# smart_switch_2021-06-13.net
KiCad netlist of a schematic drawn in EasyEDA
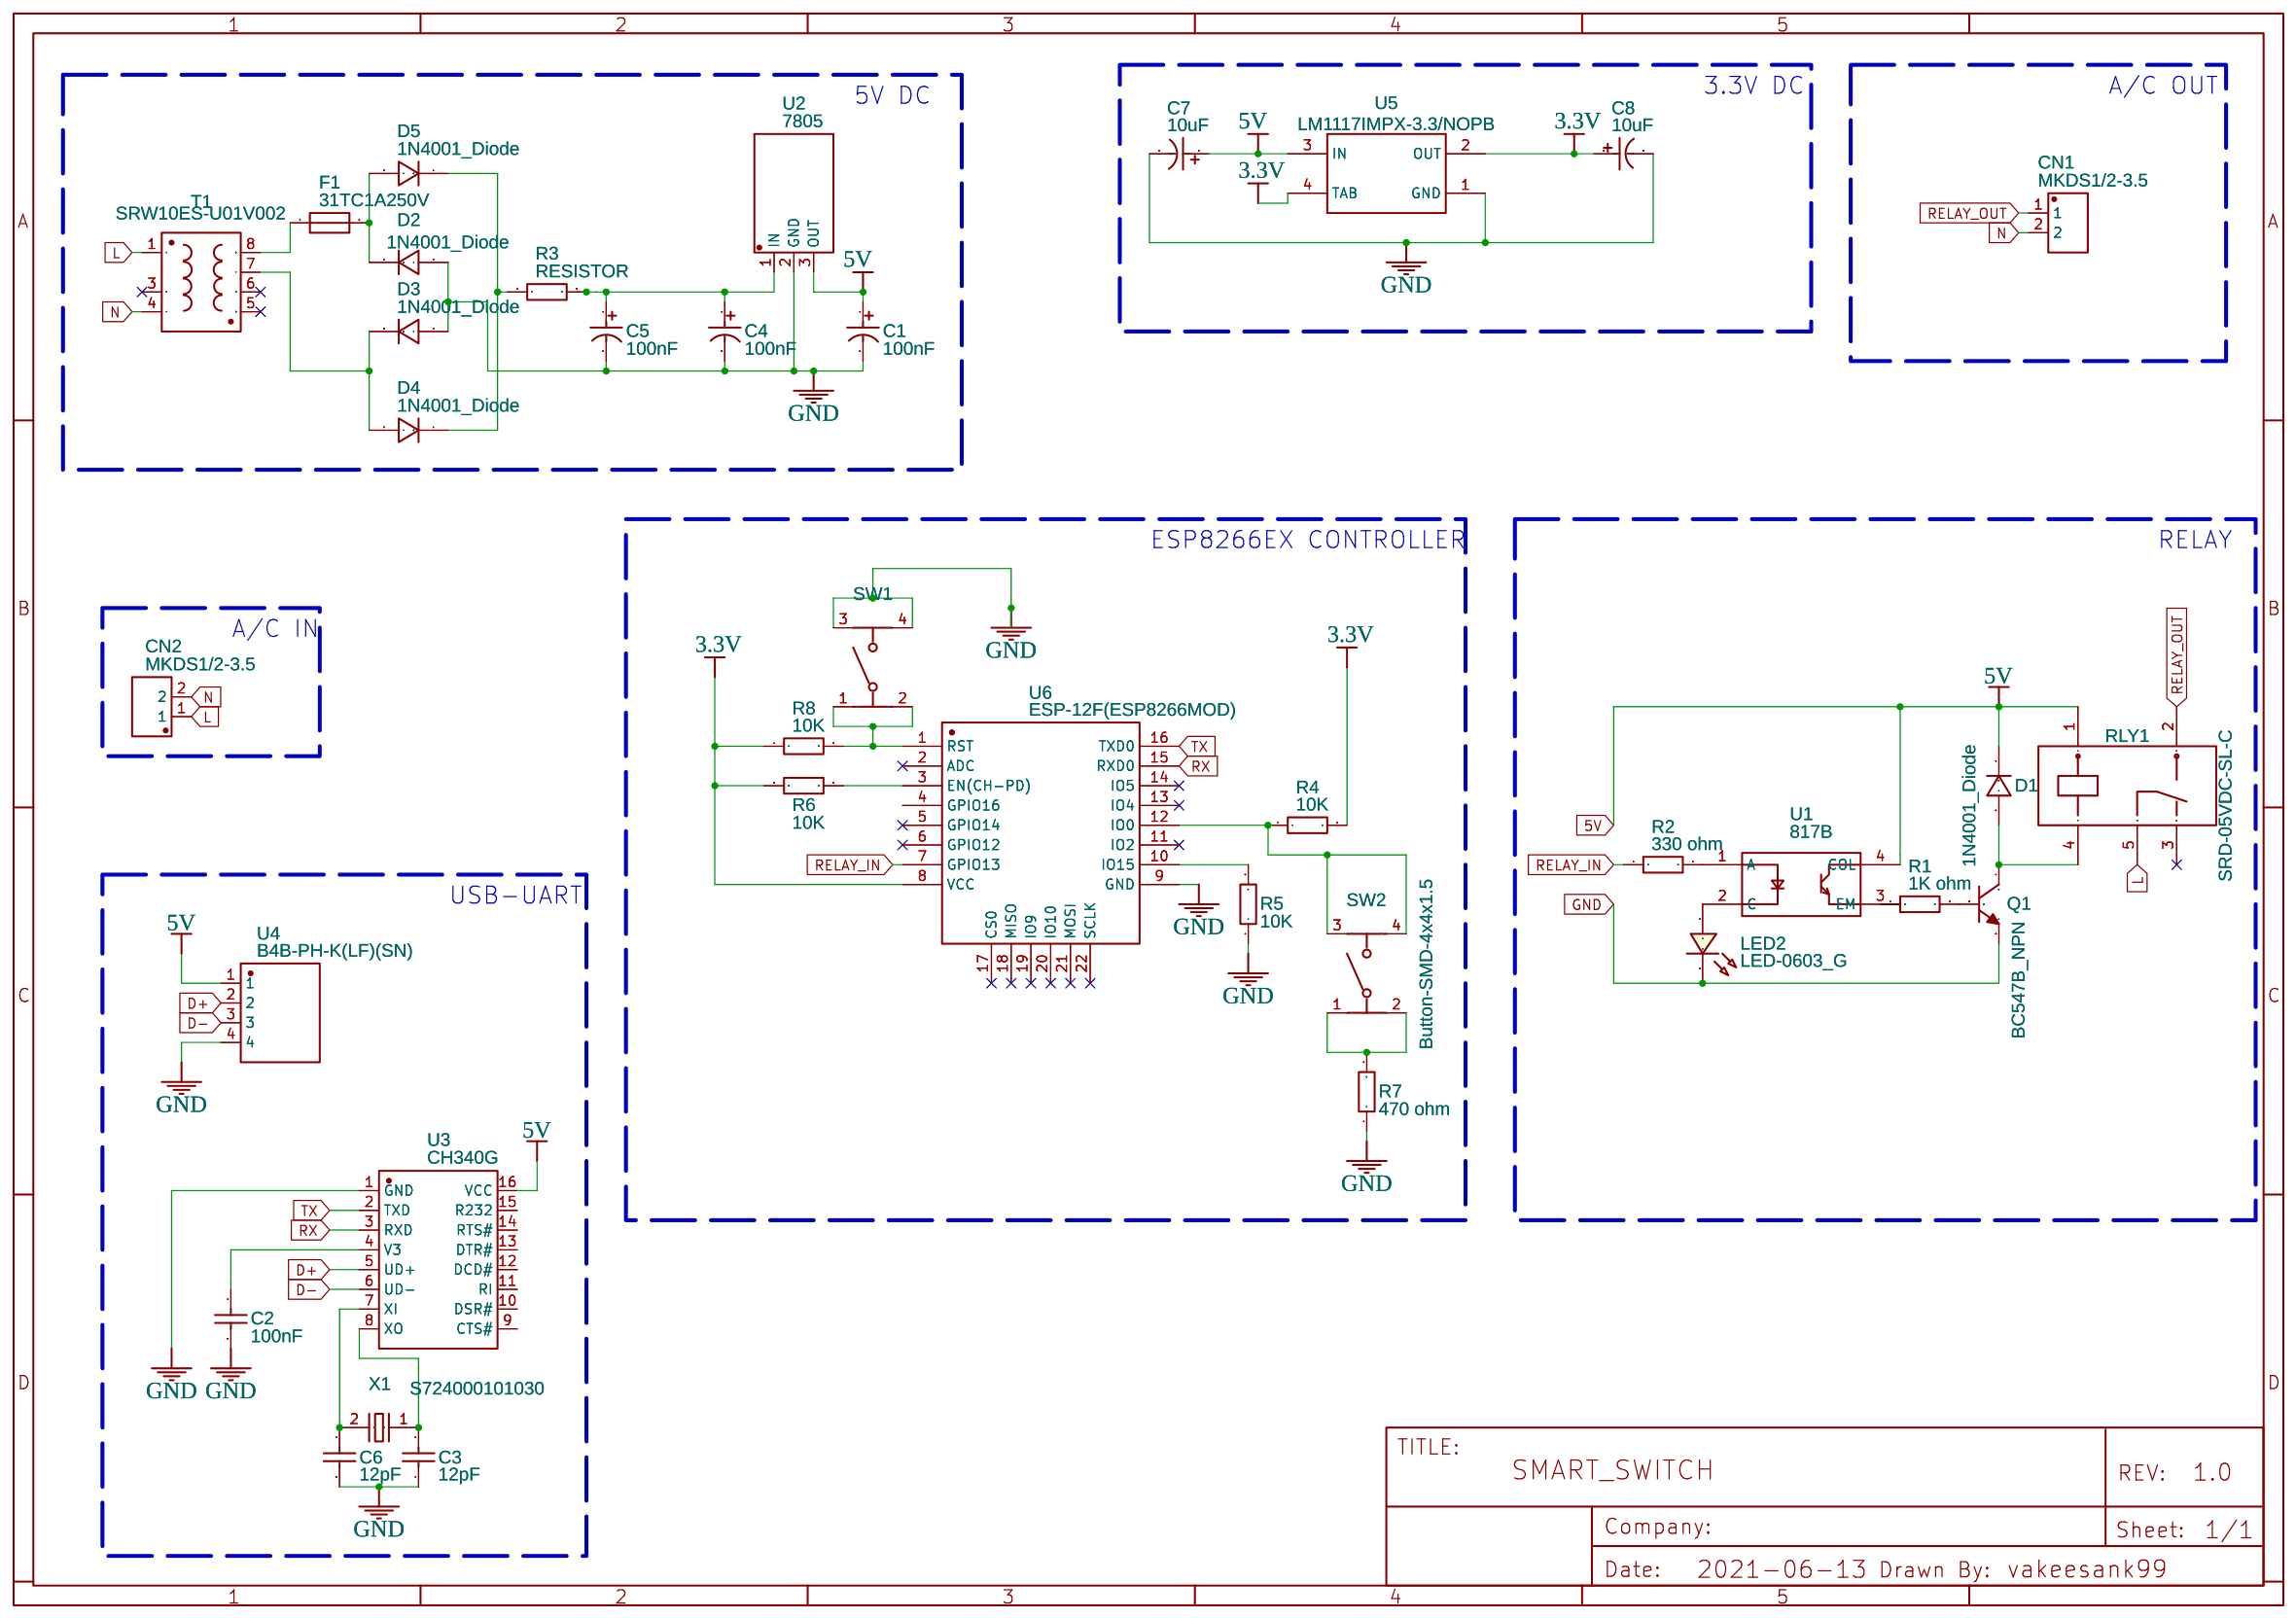
[diagram p0: schematic sheet]

(export (version "E")
  (design (tool "Eeschema 10.0.6"))
  (components
    (comp (ref "C1")
      (value "100nF")
      (fields (field (name "BOM_Manufacturer Part") "0.1UF 50V") (field (name "BOM_Supplier Part") "C28061"))
      (libsource (lib "") (part "0.1uF"))
    )
    (comp (ref "C2")
      (value "100nF")
      (fields
        (field (name "BOM_Manufacturer Part") "0.1UF(104) +-20% 63v")
        (field (name "BOM_Supplier Part") "C19355")
      )
      (libsource (lib "") (part "100nF"))
    )
    (comp (ref "C3")
      (value "12pF")
      (fields
        (field (name "BOM_Manufacturer Part") "0805CG120J500NT")
        (field (name "BOM_Supplier Part") "C38142")
      )
      (libsource (lib "") (part "0805CG120J500NT_C38142"))
    )
    (comp (ref "C4")
      (value "100nF")
      (fields (field (name "BOM_Manufacturer Part") "0.1UF 50V") (field (name "BOM_Supplier Part") "C28061"))
      (libsource (lib "") (part "0.1uF"))
    )
    (comp (ref "C5")
      (value "100nF")
      (fields (field (name "BOM_Manufacturer Part") "0.1UF 50V") (field (name "BOM_Supplier Part") "C28061"))
      (libsource (lib "") (part "0.1uF"))
    )
    (comp (ref "C6")
      (value "12pF")
      (fields
        (field (name "BOM_Manufacturer Part") "0805CG120J500NT")
        (field (name "BOM_Supplier Part") "C38142")
      )
      (libsource (lib "") (part "0805CG120J500NT_C38142"))
    )
    (comp (ref "C7")
      (value "10uF")
      (fields
        (field (name "BOM_Manufacturer Part") "10uF 16V 5*11")
        (field (name "BOM_Supplier Part") "C43799")
      )
      (libsource (lib "") (part "10uF 16V 5*11_1"))
    )
    (comp (ref "C8")
      (value "10uF")
      (fields
        (field (name "BOM_Manufacturer Part") "10uF 16V 5*11")
        (field (name "BOM_Supplier Part") "C43799")
      )
      (libsource (lib "") (part "10uF 16V 5*11"))
    )
    (comp (ref "CN1")
      (value "MKDS1/2-3.5")
      (fields (field (name "BOM_Supplier Part") "C89122"))
      (libsource (lib "") (part "MKDS1/2-3.5"))
    )
    (comp (ref "CN2")
      (value "MKDS1/2-3.5")
      (fields (field (name "BOM_Supplier Part") "C89122"))
      (libsource (lib "") (part "MKDS1/2-3.5_1"))
    )
    (comp (ref "D1")
      (value "1N4001_Diode")
      (fields (field (name "BOM_Manufacturer Part") "1N4001-T") (field (name "BOM_Supplier Part") "C99656"))
      (libsource (lib "") (part "1N4001_Diode_2"))
    )
    (comp (ref "D2")
      (value "1N4001_Diode")
      (fields (field (name "BOM_Manufacturer Part") "1N4001-T") (field (name "BOM_Supplier Part") "C99656"))
      (libsource (lib "") (part "1N4001_Diode"))
    )
    (comp (ref "D3")
      (value "1N4001_Diode")
      (fields (field (name "BOM_Manufacturer Part") "1N4001-T") (field (name "BOM_Supplier Part") "C99656"))
      (libsource (lib "") (part "1N4001_Diode"))
    )
    (comp (ref "D4")
      (value "1N4001_Diode")
      (fields (field (name "BOM_Manufacturer Part") "1N4001-T") (field (name "BOM_Supplier Part") "C99656"))
      (libsource (lib "") (part "1N4001_Diode_1"))
    )
    (comp (ref "D5")
      (value "1N4001_Diode")
      (fields (field (name "BOM_Manufacturer Part") "1N4001-T") (field (name "BOM_Supplier Part") "C99656"))
      (libsource (lib "") (part "1N4001_Diode_1"))
    )
    (comp (ref "F1")
      (value "31TC1A250V")
      (fields (field (name "BOM_Supplier Part") "C529652"))
      (libsource (lib "") (part "31TC1A250V"))
    )
    (comp (ref "LED2")
      (value "LED-0603_G")
      (fields
        (field (name "BOM_Manufacturer Part") "19-217/GHC-YR1S2/3T")
        (field (name "BOM_Supplier Part") "C72043")
      )
      (libsource (lib "") (part "LED-0603_G"))
    )
    (comp (ref "Q1")
      (value "BC547B_NPN")
      (fields (field (name "BOM_Manufacturer Part") "BC547B") (field (name "BOM_Supplier Part") "C713613"))
      (libsource (lib "") (part "BC547B_NPN_Transistor"))
    )
    (comp (ref "R1")
      (value "1K ohm")
      (fields
        (field (name "BOM_Manufacturer Part") "MFR0W4F2200A50")
        (field (name "BOM_Supplier Part") "E57439")
      )
      (libsource (lib "") (part "RESISTOR"))
    )
    (comp (ref "R2")
      (value "330 ohm")
      (fields
        (field (name "BOM_Manufacturer Part") "MFR0W4F2200A50")
        (field (name "BOM_Supplier Part") "E57439")
      )
      (libsource (lib "") (part "RESISTOR"))
    )
    (comp (ref "R3")
      (value "RESISTOR")
      (fields
        (field (name "BOM_Manufacturer Part") "MFR0W4F2200A50")
        (field (name "BOM_Supplier Part") "E57439")
      )
      (libsource (lib "") (part "RESISTOR"))
    )
    (comp (ref "R4")
      (value "10K")
      (fields
        (field (name "BOM_Manufacturer Part") "TR0402D10KQ1025")
        (field (name "BOM_Supplier Part") "C149898")
      )
      (libsource (lib "") (part "TR0402D10KQ1025_1"))
    )
    (comp (ref "R5")
      (value "10K")
      (fields
        (field (name "BOM_Manufacturer Part") "TR0402D10KQ1025")
        (field (name "BOM_Supplier Part") "C149898")
      )
      (libsource (lib "") (part "TR0402D10KQ1025"))
    )
    (comp (ref "R6")
      (value "10K")
      (fields
        (field (name "BOM_Manufacturer Part") "TR0402D10KQ1025")
        (field (name "BOM_Supplier Part") "C149898")
      )
      (libsource (lib "") (part "TR0402D10KQ1025_2"))
    )
    (comp (ref "R7")
      (value "470 ohm")
      (fields
        (field (name "BOM_Manufacturer Part") "TR0402D10KQ1025")
        (field (name "BOM_Supplier Part") "C149898")
      )
      (libsource (lib "") (part "TR0402D10KQ1025"))
    )
    (comp (ref "R8")
      (value "10K")
      (fields
        (field (name "BOM_Manufacturer Part") "TR0402D10KQ1025")
        (field (name "BOM_Supplier Part") "C149898")
      )
      (libsource (lib "") (part "TR0402D10KQ1025_1"))
    )
    (comp (ref "RLY1")
      (value "SRD-05VDC-SL-C")
      (fields (field (name "BOM_Supplier Part") "C35449"))
      (libsource (lib "") (part "SRD-05VDC-SL-C"))
    )
    (comp (ref "SW1")
      (value "Button-SMD-4x4x1.5")
      (fields
        (field (name "BOM_Manufacturer Part") "4*4*1.5Copper head,260G, 0.25mm,")
        (field (name "BOM_Supplier Part") "C71830")
      )
      (libsource (lib "") (part "Button-SMD-4x4x1.5"))
    )
    (comp (ref "SW2")
      (value "Button-SMD-4x4x1.5")
      (fields
        (field (name "BOM_Manufacturer Part") "4*4*1.5Copper head,260G, 0.25mm,")
        (field (name "BOM_Supplier Part") "C71830")
      )
      (libsource (lib "") (part "Button-SMD-4x4x1.5"))
    )
    (comp (ref "T1")
      (value "SRW10ES-U01V002")
      (fields (field (name "BOM_Supplier Part") "C433047"))
      (libsource (lib "") (part "SRW10ES-U01V002"))
    )
    (comp (ref "U1")
      (value "817B")
      (fields (field (name "BOM_Supplier Part") "C695830"))
      (libsource (lib "") (part "817B"))
    )
    (comp (ref "U2")
      (value "7805")
      (fields (field (name "BOM_Supplier Part") "C305416"))
      (libsource (lib "") (part "7805"))
    )
    (comp (ref "U3")
      (value "CH340G")
      (fields (field (name "BOM_Supplier Part") "C14267"))
      (libsource (lib "") (part "CH340G"))
    )
    (comp (ref "U4")
      (value "B4B-PH-K(LF)(SN)")
      (fields (field (name "BOM_Supplier Part") "C265289"))
      (libsource (lib "") (part "B4B-PH-K(LF)(SN)"))
    )
    (comp (ref "U5")
      (value "LM1117IMPX-3.3/NOPB")
      (fields (field (name "BOM_Supplier Part") "C23984"))
      (libsource (lib "") (part "LM1117IMPX-3.3/NOPB"))
    )
    (comp (ref "U6")
      (value "ESP-12F(ESP8266MOD)")
      (fields (field (name "BOM_Supplier Part") "C82891"))
      (libsource (lib "") (part "ESP-12F(ESP8266MOD)"))
    )
    (comp (ref "X1")
      (value "S724000101030")
      (fields (field (name "BOM_Supplier Part") "C555584"))
      (libsource (lib "") (part "S724000101030"))
    )
  )
  (nets
    (net (code "1") (name "3.3V") (class "Default")
      (node (ref "C8") (pin "1") (pinfunction "1_1") (pintype "input"))
      (node (ref "R4") (pin "2") (pinfunction "2_2") (pintype "unspecified"))
      (node (ref "R6") (pin "2") (pinfunction "2_2") (pintype "unspecified"))
      (node (ref "R8") (pin "1") (pinfunction "1_1") (pintype "unspecified"))
      (node (ref "U5") (pin "2") (pinfunction "OUT_2") (pintype "passive"))
      (node (ref "U5") (pin "4") (pinfunction "TAB_4") (pintype "passive"))
      (node (ref "U6") (pin "8") (pinfunction "VCC_8") (pintype "unspecified"))
    )
    (net (code "2") (name "5V") (class "Default")
      (node (ref "C1") (pin "1") (pinfunction "1_1") (pintype "input"))
      (node (ref "C7") (pin "1") (pinfunction "1_1") (pintype "input"))
      (node (ref "D1") (pin "1") (pinfunction "C_1") (pintype "unspecified"))
      (node (ref "RLY1") (pin "1") (pinfunction "1_1") (pintype "input"))
      (node (ref "U1") (pin "4") (pinfunction "COL_4") (pintype "unspecified"))
      (node (ref "U2") (pin "3") (pinfunction "OUT_3") (pintype "unspecified"))
      (node (ref "U3") (pin "16") (pinfunction "VCC_16") (pintype "unspecified"))
      (node (ref "U4") (pin "1") (pinfunction "1_1") (pintype "unspecified"))
      (node (ref "U5") (pin "3") (pinfunction "IN_3") (pintype "passive"))
    )
    (net (code "3") (name "D+") (class "Default")
      (node (ref "U3") (pin "5") (pinfunction "UD+_5") (pintype "unspecified"))
      (node (ref "U4") (pin "2") (pinfunction "2_2") (pintype "unspecified"))
    )
    (net (code "4") (name "D-") (class "Default")
      (node (ref "U3") (pin "6") (pinfunction "UD-_6") (pintype "unspecified"))
      (node (ref "U4") (pin "3") (pinfunction "3_3") (pintype "unspecified"))
    )
    (net (code "5") (name "GND") (class "Default")
      (node (ref "C1") (pin "2") (pinfunction "2_2") (pintype "input"))
      (node (ref "C2") (pin "2") (pinfunction "2_2") (pintype "input"))
      (node (ref "C3") (pin "1") (pinfunction "1_1") (pintype "input"))
      (node (ref "C4") (pin "2") (pinfunction "2_2") (pintype "input"))
      (node (ref "C5") (pin "2") (pinfunction "2_2") (pintype "input"))
      (node (ref "C6") (pin "1") (pinfunction "1_1") (pintype "input"))
      (node (ref "C7") (pin "2") (pinfunction "2_2") (pintype "input"))
      (node (ref "C8") (pin "2") (pinfunction "2_2") (pintype "input"))
      (node (ref "D2") (pin "2") (pinfunction "A_2") (pintype "unspecified"))
      (node (ref "D3") (pin "2") (pinfunction "A_2") (pintype "unspecified"))
      (node (ref "LED2") (pin "2") (pinfunction "2_2") (pintype "unspecified"))
      (node (ref "Q1") (pin "3") (pinfunction "E_3") (pintype "input"))
      (node (ref "R5") (pin "1") (pinfunction "1_1") (pintype "unspecified"))
      (node (ref "R7") (pin "1") (pinfunction "1_1") (pintype "unspecified"))
      (node (ref "SW1") (pin "3") (pinfunction "3_3") (pintype "unspecified"))
      (node (ref "SW1") (pin "4") (pinfunction "4_4") (pintype "unspecified"))
      (node (ref "U2") (pin "2") (pinfunction "GND_2") (pintype "unspecified"))
      (node (ref "U3") (pin "1") (pinfunction "GND_1") (pintype "unspecified"))
      (node (ref "U4") (pin "4") (pinfunction "4_4") (pintype "unspecified"))
      (node (ref "U5") (pin "1") (pinfunction "GND_1") (pintype "passive"))
      (node (ref "U6") (pin "9") (pinfunction "GND_9") (pintype "unspecified"))
    )
    (net (code "6") (name "L") (class "Default")
      (node (ref "CN2") (pin "1") (pinfunction "1_1") (pintype "unspecified"))
      (node (ref "RLY1") (pin "5") (pinfunction "5_5") (pintype "input"))
      (node (ref "T1") (pin "1") (pinfunction "1_1") (pintype "unspecified"))
    )
    (net (code "7") (name "N") (class "Default")
      (node (ref "CN1") (pin "2") (pinfunction "2_2") (pintype "unspecified"))
      (node (ref "CN2") (pin "2") (pinfunction "2_2") (pintype "unspecified"))
      (node (ref "T1") (pin "4") (pinfunction "4_4") (pintype "unspecified"))
    )
    (net (code "8") (name "Net-(D1-A)") (class "Default")
      (node (ref "D1") (pin "2") (pinfunction "A_2") (pintype "unspecified"))
      (node (ref "Q1") (pin "1") (pinfunction "C_1") (pintype "input"))
      (node (ref "RLY1") (pin "4") (pinfunction "4_4") (pintype "input"))
    )
    (net (code "9") (name "Net-(D2-C)") (class "Default")
      (node (ref "D2") (pin "1") (pinfunction "C_1") (pintype "unspecified"))
      (node (ref "D5") (pin "2") (pinfunction "A_2") (pintype "unspecified"))
      (node (ref "F1") (pin "2") (pinfunction "2_2") (pintype "unspecified"))
    )
    (net (code "10") (name "Net-(D3-C)") (class "Default")
      (node (ref "D3") (pin "1") (pinfunction "C_1") (pintype "unspecified"))
      (node (ref "D4") (pin "2") (pinfunction "A_2") (pintype "unspecified"))
      (node (ref "T1") (pin "7") (pinfunction "7_7") (pintype "unspecified"))
    )
    (net (code "11") (name "Net-(D4-C)") (class "Default")
      (node (ref "D4") (pin "1") (pinfunction "C_1") (pintype "unspecified"))
      (node (ref "D5") (pin "1") (pinfunction "C_1") (pintype "unspecified"))
      (node (ref "R3") (pin "1") (pinfunction "1_1") (pintype "input"))
    )
    (net (code "12") (name "Net-(F1-Pad1)") (class "Default")
      (node (ref "F1") (pin "1") (pinfunction "1_1") (pintype "unspecified"))
      (node (ref "T1") (pin "8") (pinfunction "8_8") (pintype "unspecified"))
    )
    (net (code "13") (name "Net-(Q1-B)") (class "Default")
      (node (ref "Q1") (pin "2") (pinfunction "B_2") (pintype "input"))
      (node (ref "R1") (pin "2") (pinfunction "2_2") (pintype "input"))
    )
    (net (code "14") (name "Net-(R7-Pad2)") (class "Default")
      (node (ref "R7") (pin "2") (pinfunction "2_2") (pintype "unspecified"))
      (node (ref "SW2") (pin "1") (pinfunction "1_1") (pintype "unspecified"))
      (node (ref "SW2") (pin "2") (pinfunction "2_2") (pintype "unspecified"))
    )
    (net (code "15") (name "Net-(U1-A)") (class "Default")
      (node (ref "R2") (pin "2") (pinfunction "2_2") (pintype "input"))
      (node (ref "U1") (pin "1") (pinfunction "A_1") (pintype "unspecified"))
    )
    (net (code "16") (name "Net-(U1-C)") (class "Default")
      (node (ref "LED2") (pin "1") (pinfunction "1_1") (pintype "unspecified"))
      (node (ref "U1") (pin "2") (pinfunction "C_2") (pintype "unspecified"))
    )
    (net (code "17") (name "Net-(U1-EM)") (class "Default")
      (node (ref "R1") (pin "1") (pinfunction "1_1") (pintype "input"))
      (node (ref "U1") (pin "3") (pinfunction "EM_3") (pintype "unspecified"))
    )
    (net (code "18") (name "Net-(U2-IN)") (class "Default")
      (node (ref "C4") (pin "1") (pinfunction "1_1") (pintype "input"))
      (node (ref "C5") (pin "1") (pinfunction "1_1") (pintype "input"))
      (node (ref "R3") (pin "2") (pinfunction "2_2") (pintype "input"))
      (node (ref "U2") (pin "1") (pinfunction "IN_1") (pintype "unspecified"))
    )
    (net (code "19") (name "Net-(U3-V3)") (class "Default")
      (node (ref "C2") (pin "1") (pinfunction "1_1") (pintype "input"))
      (node (ref "U3") (pin "4") (pinfunction "V3_4") (pintype "unspecified"))
    )
    (net (code "20") (name "Net-(U3-XI)") (class "Default")
      (node (ref "C6") (pin "2") (pinfunction "2_2") (pintype "input"))
      (node (ref "U3") (pin "7") (pinfunction "XI_7") (pintype "unspecified"))
      (node (ref "X1") (pin "2") (pinfunction "GND_2") (pintype "input"))
    )
    (net (code "21") (name "Net-(U3-XO)") (class "Default")
      (node (ref "C3") (pin "2") (pinfunction "2_2") (pintype "input"))
      (node (ref "U3") (pin "8") (pinfunction "XO_8") (pintype "unspecified"))
      (node (ref "X1") (pin "1") (pinfunction "1_1") (pintype "input"))
    )
    (net (code "22") (name "Net-(U6-EN(CH-PD))") (class "Default")
      (node (ref "R6") (pin "1") (pinfunction "1_1") (pintype "unspecified"))
      (node (ref "U6") (pin "3") (pinfunction "EN(CH-PD)_3") (pintype "unspecified"))
    )
    (net (code "23") (name "Net-(U6-IO0)") (class "Default")
      (node (ref "R4") (pin "1") (pinfunction "1_1") (pintype "unspecified"))
      (node (ref "SW2") (pin "3") (pinfunction "3_3") (pintype "unspecified"))
      (node (ref "SW2") (pin "4") (pinfunction "4_4") (pintype "unspecified"))
      (node (ref "U6") (pin "12") (pinfunction "IO0_12") (pintype "unspecified"))
    )
    (net (code "24") (name "Net-(U6-IO15)") (class "Default")
      (node (ref "R5") (pin "2") (pinfunction "2_2") (pintype "unspecified"))
      (node (ref "U6") (pin "10") (pinfunction "IO15_10") (pintype "unspecified"))
    )
    (net (code "25") (name "Net-(U6-RST)") (class "Default")
      (node (ref "R8") (pin "2") (pinfunction "2_2") (pintype "unspecified"))
      (node (ref "SW1") (pin "1") (pinfunction "1_1") (pintype "unspecified"))
      (node (ref "SW1") (pin "2") (pinfunction "2_2") (pintype "unspecified"))
      (node (ref "U6") (pin "1") (pinfunction "RST_1") (pintype "unspecified"))
    )
    (net (code "26") (name "RELAY_IN") (class "Default")
      (node (ref "R2") (pin "1") (pinfunction "1_1") (pintype "input"))
      (node (ref "U6") (pin "7") (pinfunction "GPIO13_7") (pintype "unspecified"))
    )
    (net (code "27") (name "RELAY_OUT") (class "Default")
      (node (ref "CN1") (pin "1") (pinfunction "1_1") (pintype "unspecified"))
      (node (ref "RLY1") (pin "2") (pinfunction "2_2") (pintype "input"))
    )
    (net (code "28") (name "RX") (class "Default")
      (node (ref "U3") (pin "3") (pinfunction "RXD_3") (pintype "unspecified"))
      (node (ref "U6") (pin "15") (pinfunction "RXD0_15") (pintype "unspecified"))
    )
    (net (code "29") (name "TX") (class "Default")
      (node (ref "U3") (pin "2") (pinfunction "TXD_2") (pintype "unspecified"))
      (node (ref "U6") (pin "16") (pinfunction "TXD0_16") (pintype "unspecified"))
    )
    (net (code "30") (name "unconnected-(RLY1-Pad3)") (class "Default")
      (node (ref "RLY1") (pin "3") (pinfunction "3_3") (pintype "input+no_connect"))
    )
    (net (code "31") (name "unconnected-(T1-Pad3)") (class "Default")
      (node (ref "T1") (pin "3") (pinfunction "3_3") (pintype "unspecified+no_connect"))
    )
    (net (code "32") (name "unconnected-(T1-Pad5)") (class "Default")
      (node (ref "T1") (pin "5") (pinfunction "5_5") (pintype "unspecified+no_connect"))
    )
    (net (code "33") (name "unconnected-(T1-Pad6)") (class "Default")
      (node (ref "T1") (pin "6") (pinfunction "6_6") (pintype "unspecified+no_connect"))
    )
    (net (code "34") (name "unconnected-(U3-CTS#-Pad9)") (class "Default")
      (node (ref "U3") (pin "9") (pinfunction "CTS#_9") (pintype "unspecified"))
    )
    (net (code "35") (name "unconnected-(U3-DCD#-Pad12)") (class "Default")
      (node (ref "U3") (pin "12") (pinfunction "DCD#_12") (pintype "unspecified"))
    )
    (net (code "36") (name "unconnected-(U3-DSR#-Pad10)") (class "Default")
      (node (ref "U3") (pin "10") (pinfunction "DSR#_10") (pintype "unspecified"))
    )
    (net (code "37") (name "unconnected-(U3-DTR#-Pad13)") (class "Default")
      (node (ref "U3") (pin "13") (pinfunction "DTR#_13") (pintype "unspecified"))
    )
    (net (code "38") (name "unconnected-(U3-R232-Pad15)") (class "Default")
      (node (ref "U3") (pin "15") (pinfunction "R232_15") (pintype "unspecified"))
    )
    (net (code "39") (name "unconnected-(U3-RI-Pad11)") (class "Default")
      (node (ref "U3") (pin "11") (pinfunction "RI_11") (pintype "unspecified"))
    )
    (net (code "40") (name "unconnected-(U3-RTS#-Pad14)") (class "Default")
      (node (ref "U3") (pin "14") (pinfunction "RTS#_14") (pintype "unspecified"))
    )
    (net (code "41") (name "unconnected-(U6-ADC-Pad2)") (class "Default")
      (node (ref "U6") (pin "2") (pinfunction "ADC_2") (pintype "unspecified+no_connect"))
    )
    (net (code "42") (name "unconnected-(U6-CS0-Pad17)") (class "Default")
      (node (ref "U6") (pin "17") (pinfunction "CS0_17") (pintype "unspecified+no_connect"))
    )
    (net (code "43") (name "unconnected-(U6-GPIO12-Pad6)") (class "Default")
      (node (ref "U6") (pin "6") (pinfunction "GPIO12_6") (pintype "unspecified+no_connect"))
    )
    (net (code "44") (name "unconnected-(U6-GPIO14-Pad5)") (class "Default")
      (node (ref "U6") (pin "5") (pinfunction "GPIO14_5") (pintype "unspecified+no_connect"))
    )
    (net (code "45") (name "unconnected-(U6-GPIO16-Pad4)") (class "Default")
      (node (ref "U6") (pin "4") (pinfunction "GPIO16_4") (pintype "unspecified"))
    )
    (net (code "46") (name "unconnected-(U6-IO2-Pad11)") (class "Default")
      (node (ref "U6") (pin "11") (pinfunction "IO2_11") (pintype "unspecified+no_connect"))
    )
    (net (code "47") (name "unconnected-(U6-IO4-Pad13)") (class "Default")
      (node (ref "U6") (pin "13") (pinfunction "IO4_13") (pintype "unspecified+no_connect"))
    )
    (net (code "48") (name "unconnected-(U6-IO5-Pad14)") (class "Default")
      (node (ref "U6") (pin "14") (pinfunction "IO5_14") (pintype "unspecified+no_connect"))
    )
    (net (code "49") (name "unconnected-(U6-IO9-Pad19)") (class "Default")
      (node (ref "U6") (pin "19") (pinfunction "IO9_19") (pintype "unspecified+no_connect"))
    )
    (net (code "50") (name "unconnected-(U6-IO10-Pad20)") (class "Default")
      (node (ref "U6") (pin "20") (pinfunction "IO10_20") (pintype "unspecified+no_connect"))
    )
    (net (code "51") (name "unconnected-(U6-MISO-Pad18)") (class "Default")
      (node (ref "U6") (pin "18") (pinfunction "MISO_18") (pintype "unspecified+no_connect"))
    )
    (net (code "52") (name "unconnected-(U6-MOSI-Pad21)") (class "Default")
      (node (ref "U6") (pin "21") (pinfunction "MOSI_21") (pintype "unspecified+no_connect"))
    )
    (net (code "53") (name "unconnected-(U6-SCLK-Pad22)") (class "Default")
      (node (ref "U6") (pin "22") (pinfunction "SCLK_22") (pintype "unspecified+no_connect"))
    )
  )
)
